# Main.net
KiCad netlist of a schematic drawn in Altium Designer
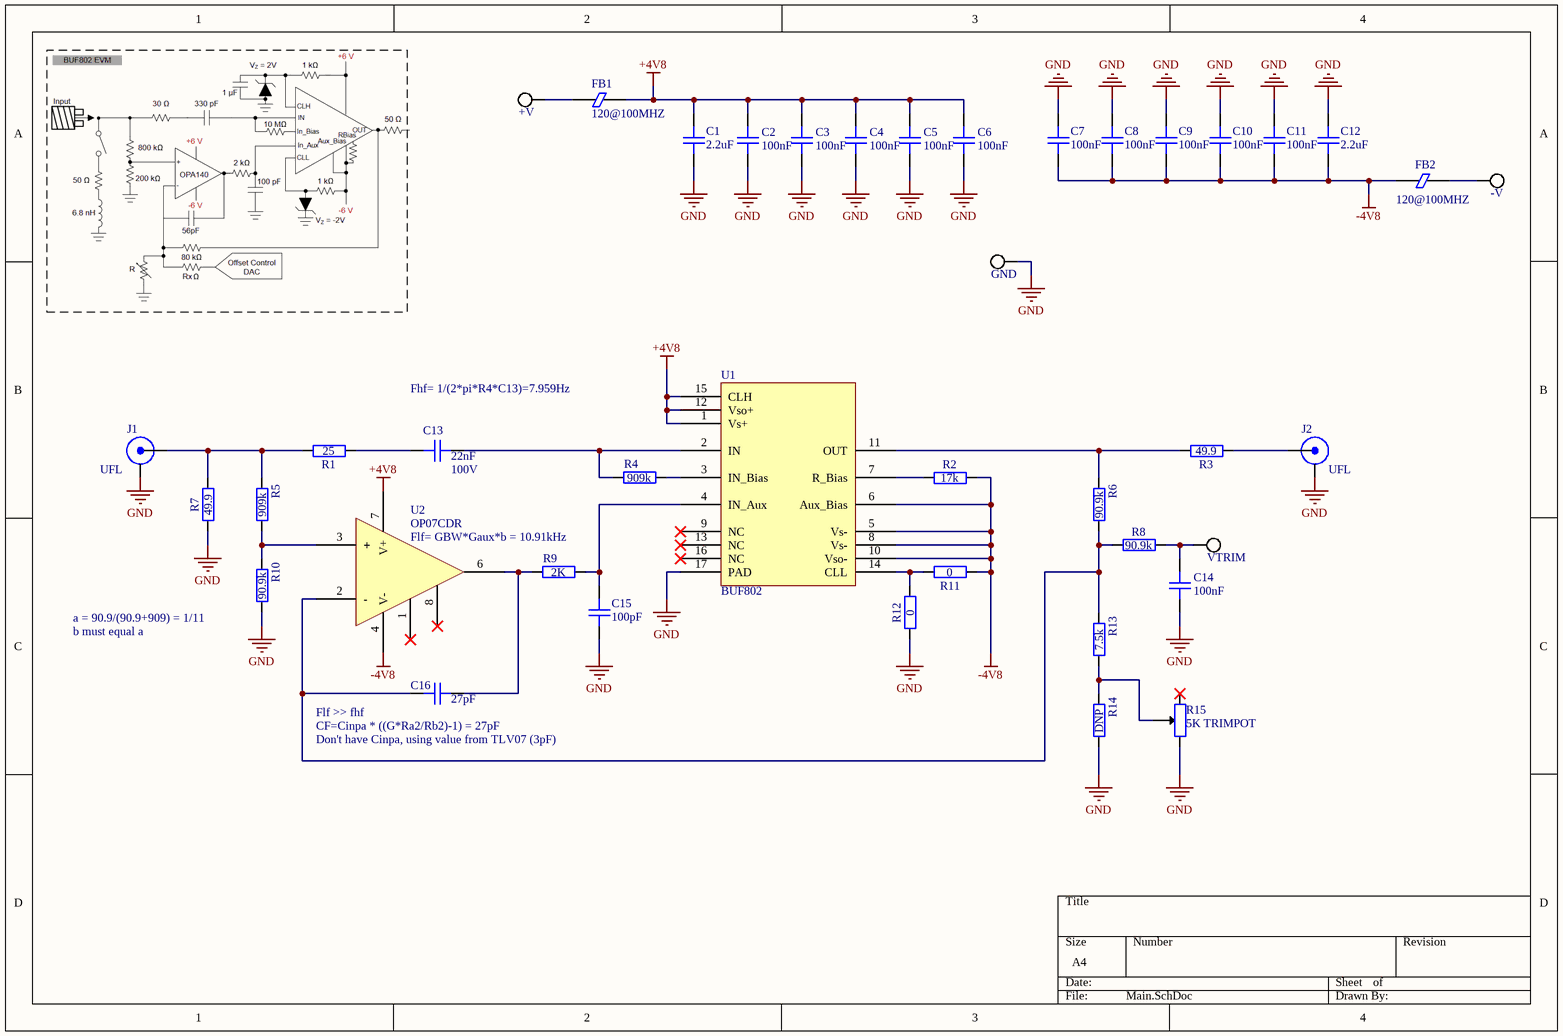
[diagram p0: Main.SchDoc]

(export (version "E")
  (design (tool "Eeschema 10.0.6"))
  (components
    (comp (ref "+V") (value "PCB") (footprint "GEN_TP_PCB") (libsource (lib "DSO") (part "TP PCB 1mm")))
    (comp (ref "-V") (value "PCB") (footprint "GEN_TP_PCB") (libsource (lib "DSO") (part "TP PCB 1mm")))
    (comp (ref "C1")
      (value "2.2uF")
      (footprint "GEN_C_0402")
      (libsource (lib "DSO") (part "CAP 2.2uF 10V X5R 0402"))
    )
    (comp (ref "C2")
      (value "100nF")
      (footprint "GEN_C_0402")
      (libsource (lib "DSO") (part "CAP 100nF 16V X7R 0402"))
    )
    (comp (ref "C3")
      (value "100nF")
      (footprint "GEN_C_0402")
      (libsource (lib "DSO") (part "CAP 100nF 16V X7R 0402"))
    )
    (comp (ref "C4")
      (value "100nF")
      (footprint "GEN_C_0402")
      (libsource (lib "DSO") (part "CAP 100nF 16V X7R 0402"))
    )
    (comp (ref "C5")
      (value "100nF")
      (footprint "GEN_C_0402")
      (libsource (lib "DSO") (part "CAP 100nF 16V X7R 0402"))
    )
    (comp (ref "C6")
      (value "100nF")
      (footprint "GEN_C_0402")
      (libsource (lib "DSO") (part "CAP 100nF 16V X7R 0402"))
    )
    (comp (ref "C7")
      (value "100nF")
      (footprint "GEN_C_0402")
      (libsource (lib "DSO") (part "CAP 100nF 16V X7R 0402"))
    )
    (comp (ref "C8")
      (value "100nF")
      (footprint "GEN_C_0402")
      (libsource (lib "DSO") (part "CAP 100nF 16V X7R 0402"))
    )
    (comp (ref "C9")
      (value "100nF")
      (footprint "GEN_C_0402")
      (libsource (lib "DSO") (part "CAP 100nF 16V X7R 0402"))
    )
    (comp (ref "C10")
      (value "100nF")
      (footprint "GEN_C_0402")
      (libsource (lib "DSO") (part "CAP 100nF 16V X7R 0402"))
    )
    (comp (ref "C11")
      (value "100nF")
      (footprint "GEN_C_0402")
      (libsource (lib "DSO") (part "CAP 100nF 16V X7R 0402"))
    )
    (comp (ref "C12")
      (value "2.2uF")
      (footprint "GEN_C_0402")
      (libsource (lib "DSO") (part "CAP 2.2uF 10V X5R 0402"))
    )
    (comp (ref "C13")
      (value "22nF")
      (footprint "GEN_C_0603")
      (fields (field (name "VOLTAGE RATING") "100V"))
      (libsource (lib "DSO") (part "CAP 22nF 100V X7R 0603"))
    )
    (comp (ref "C14")
      (value "100nF")
      (footprint "GEN_C_0402")
      (libsource (lib "DSO") (part "CAP 100nF 16V X7R 0402"))
    )
    (comp (ref "C15")
      (value "100pF")
      (footprint "GEN_C_0402")
      (libsource (lib "DSO") (part "CAP 100pF 50V C0G 0402"))
    )
    (comp (ref "C16") (value "27pF") (footprint "GEN_C_0402") (libsource (lib "DSO") (part "CAP TBD 0402")))
    (comp (ref "FB1")
      (value "120@100MHZ")
      (footprint "GEN_R_0402")
      (libsource (lib "DSO") (part "FERRITE BEAD 120 OHM 0402"))
    )
    (comp (ref "FB2")
      (value "120@100MHZ")
      (footprint "GEN_R_0402")
      (libsource (lib "DSO") (part "FERRITE BEAD 120 OHM 0402"))
    )
    (comp (ref "GND") (value "PCB") (footprint "GEN_TP_PCB") (libsource (lib "DSO") (part "TP PCB 1mm")))
    (comp (ref "J1") (value "UFL") (footprint "TE_2334884-1") (libsource (lib "DSO") (part "UFL Jack SMD")))
    (comp (ref "J2") (value "UFL") (footprint "TE_2334884-1") (libsource (lib "DSO") (part "UFL Jack SMD")))
    (comp (ref "R1")
      (value "25")
      (footprint "GEN_R_0402")
      (fields (field (name "TOLERANCE") "1%"))
      (libsource (lib "DSO") (part "RES 49.9 OHM 1% 1/10W 0402"))
    )
    (comp (ref "R2")
      (value "17k")
      (footprint "GEN_R_0402")
      (fields (field (name "TOLERANCE") "1%"))
      (libsource (lib "DSO") (part "RES 100K OHM 1% 1/10W 0402"))
    )
    (comp (ref "R3")
      (value "49.9")
      (footprint "GEN_R_0402")
      (fields (field (name "TOLERANCE") "1%"))
      (libsource (lib "DSO") (part "RES 49.9 OHM 1% 1/10W 0402"))
    )
    (comp (ref "R4")
      (value "909k")
      (footprint "GEN_R_0402")
      (fields (field (name "TOLERANCE") "1%"))
      (libsource (lib "DSO") (part "RES 909K OHM 1% 1/16W 0402"))
    )
    (comp (ref "R5")
      (value "909k")
      (footprint "GEN_R_0402")
      (fields (field (name "TOLERANCE") "1%"))
      (libsource (lib "") (part "RES 909K OHM 1% 1/16W 0402_1"))
    )
    (comp (ref "R6")
      (value "90.9k")
      (footprint "GEN_R_0402")
      (fields (field (name "TOLERANCE") "1%"))
      (libsource (lib "DSO") (part "RES 90.9K OHM 1% 1/16W 0402"))
    )
    (comp (ref "R7")
      (value "49.9")
      (footprint "GEN_R_0402")
      (fields (field (name "TOLERANCE") "1%"))
      (libsource (lib "") (part "RES 49.9 OHM 1% 1/10W 0402_1"))
    )
    (comp (ref "R8")
      (value "90.9k")
      (footprint "GEN_R_0402")
      (fields (field (name "TOLERANCE") "1%"))
      (libsource (lib "") (part "RES 90.9K OHM 1% 1/16W 0402_1"))
    )
    (comp (ref "R9")
      (value "2K")
      (footprint "GEN_R_0402")
      (fields (field (name "TOLERANCE") "1%"))
      (libsource (lib "DSO") (part "RES 2K OHM 1% 1/16W 0402"))
    )
    (comp (ref "R10")
      (value "90.9k")
      (footprint "GEN_R_0402")
      (fields (field (name "TOLERANCE") "1%"))
      (libsource (lib "DSO") (part "RES 90.9K OHM 1% 1/16W 0402"))
    )
    (comp (ref "R11")
      (value "0")
      (footprint "GEN_R_0402")
      (libsource (lib "DSO") (part "RES 0 OHM 1/16W 0402"))
    )
    (comp (ref "R12")
      (value "0")
      (footprint "GEN_R_0402")
      (libsource (lib "") (part "RES 0 OHM 1/16W 0402_1"))
    )
    (comp (ref "R13")
      (value "7.5k")
      (footprint "GEN_R_0402")
      (fields (field (name "TOLERANCE") "1%"))
      (libsource (lib "DSO") (part "RES 10K OHM 1% 1/10W 0402"))
    )
    (comp (ref "R14")
      (value "DNP")
      (footprint "GEN_R_0402")
      (fields (field (name "TOLERANCE") "1%"))
      (libsource (lib "DSO") (part "RES DNP 0402"))
    )
    (comp (ref "R15")
      (value "5K TRIMPOT")
      (footprint "BOU_3mm_POT")
      (fields (field (name "TOLERANCE") "1%"))
      (libsource (lib "DSO") (part "TRIMMER 5K OHM 0.1W J LEAD TOP"))
    )
    (comp (ref "U1")
      (value "BUF802")
      (footprint "TI_VQFN_RGT0016C")
      (libsource (lib "DSO") (part "IC BUFFER AMP BUF802"))
    )
    (comp (ref "U2")
      (value "OP07CDR")
      (footprint "TI_SOIC8_D0008A")
      (libsource (lib "DSO") (part "IC OPAMP OP07CDR"))
    )
    (comp (ref "VTRIM") (value "PCB") (footprint "GEN_TP_PCB") (libsource (lib "DSO") (part "TP PCB 1mm")))
  )
  (nets
    (net (code "1") (name "+4V8") (class "Default")
      (node (ref "C1") (pin "2") (pinfunction "2_2") (pintype "passive"))
      (node (ref "C2") (pin "1") (pinfunction "1_1") (pintype "passive"))
      (node (ref "C3") (pin "1") (pinfunction "1_1") (pintype "passive"))
      (node (ref "C4") (pin "1") (pinfunction "1_1") (pintype "passive"))
      (node (ref "C5") (pin "2") (pinfunction "2_2") (pintype "passive"))
      (node (ref "C6") (pin "2") (pinfunction "2_2") (pintype "passive"))
      (node (ref "FB1") (pin "2") (pinfunction "2_2") (pintype "passive"))
      (node (ref "U1") (pin "1") (pinfunction "Vs+_1") (pintype "passive"))
      (node (ref "U1") (pin "12") (pinfunction "Vso+_12") (pintype "passive"))
      (node (ref "U1") (pin "15") (pinfunction "CLH_15") (pintype "passive"))
      (node (ref "U2") (pin "7") (pinfunction "V+_7") (pintype "passive"))
    )
    (net (code "2") (name "-4V8") (class "Default")
      (node (ref "C10") (pin "1") (pinfunction "1_1") (pintype "passive"))
      (node (ref "C11") (pin "1") (pinfunction "1_1") (pintype "passive"))
      (node (ref "C12") (pin "2") (pinfunction "2_2") (pintype "passive"))
      (node (ref "C7") (pin "2") (pinfunction "2_2") (pintype "passive"))
      (node (ref "C8") (pin "2") (pinfunction "2_2") (pintype "passive"))
      (node (ref "C9") (pin "1") (pinfunction "1_1") (pintype "passive"))
      (node (ref "FB2") (pin "1") (pinfunction "1_1") (pintype "passive"))
      (node (ref "R11") (pin "1") (pinfunction "1_1") (pintype "passive"))
      (node (ref "R2") (pin "2") (pinfunction "2_2") (pintype "passive"))
      (node (ref "U1") (pin "10") (pinfunction "Vso-_10") (pintype "passive"))
      (node (ref "U1") (pin "5") (pinfunction "Vs-_5") (pintype "passive"))
      (node (ref "U1") (pin "6") (pinfunction "Aux_Bias_6") (pintype "passive"))
      (node (ref "U1") (pin "8") (pinfunction "Vs-_8") (pintype "passive"))
      (node (ref "U2") (pin "4") (pinfunction "V-_4") (pintype "passive"))
    )
    (net (code "3") (name "GND") (class "Default")
      (node (ref "C1") (pin "1") (pinfunction "1_1") (pintype "passive"))
      (node (ref "C10") (pin "2") (pinfunction "2_2") (pintype "passive"))
      (node (ref "C11") (pin "2") (pinfunction "2_2") (pintype "passive"))
      (node (ref "C12") (pin "1") (pinfunction "1_1") (pintype "passive"))
      (node (ref "C14") (pin "2") (pinfunction "2_2") (pintype "passive"))
      (node (ref "C15") (pin "1") (pinfunction "1_1") (pintype "passive"))
      (node (ref "C2") (pin "2") (pinfunction "2_2") (pintype "passive"))
      (node (ref "C3") (pin "2") (pinfunction "2_2") (pintype "passive"))
      (node (ref "C4") (pin "2") (pinfunction "2_2") (pintype "passive"))
      (node (ref "C5") (pin "1") (pinfunction "1_1") (pintype "passive"))
      (node (ref "C6") (pin "1") (pinfunction "1_1") (pintype "passive"))
      (node (ref "C7") (pin "1") (pinfunction "1_1") (pintype "passive"))
      (node (ref "C8") (pin "1") (pinfunction "1_1") (pintype "passive"))
      (node (ref "C9") (pin "2") (pinfunction "2_2") (pintype "passive"))
      (node (ref "GND") (pin "1") (pinfunction "1_1") (pintype "passive"))
      (node (ref "J1") (pin "2") (pinfunction "SHIELD_2") (pintype "passive"))
      (node (ref "J2") (pin "2") (pinfunction "SHIELD_2") (pintype "passive"))
      (node (ref "R10") (pin "1") (pinfunction "1_1") (pintype "passive"))
      (node (ref "R12") (pin "1") (pinfunction "1_1") (pintype "passive"))
      (node (ref "R14") (pin "1") (pinfunction "1_1") (pintype "passive"))
      (node (ref "R15") (pin "3") (pinfunction "3_3") (pintype "passive"))
      (node (ref "R7") (pin "1") (pinfunction "1_1") (pintype "passive"))
      (node (ref "U1") (pin "17") (pinfunction "PAD_17") (pintype "passive"))
    )
    (net (code "4") (name "Net-(+V-Pad1)") (class "Default")
      (node (ref "+V") (pin "1") (pinfunction "1_1") (pintype "passive"))
      (node (ref "FB1") (pin "1") (pinfunction "1_1") (pintype "passive"))
    )
    (net (code "5") (name "Net-(-V-Pad1)") (class "Default")
      (node (ref "-V") (pin "1") (pinfunction "1_1") (pintype "passive"))
      (node (ref "FB2") (pin "2") (pinfunction "2_2") (pintype "passive"))
    )
    (net (code "6") (name "Net-(C13-Pad2)") (class "Default")
      (node (ref "C13") (pin "2") (pinfunction "2_2") (pintype "passive"))
      (node (ref "R1") (pin "2") (pinfunction "2_2") (pintype "passive"))
    )
    (net (code "7") (name "Net-(C14-Pad1)") (class "Default")
      (node (ref "C14") (pin "1") (pinfunction "1_1") (pintype "passive"))
      (node (ref "R8") (pin "1") (pinfunction "1_1") (pintype "passive"))
      (node (ref "VTRIM") (pin "1") (pinfunction "1_1") (pintype "passive"))
    )
    (net (code "8") (name "Net-(J1-Signal)") (class "Default")
      (node (ref "J1") (pin "1") (pinfunction "Signal_1") (pintype "passive"))
      (node (ref "R1") (pin "1") (pinfunction "1_1") (pintype "passive"))
      (node (ref "R5") (pin "2") (pinfunction "2_2") (pintype "passive"))
      (node (ref "R7") (pin "2") (pinfunction "2_2") (pintype "passive"))
    )
    (net (code "9") (name "Net-(J2-Signal)") (class "Default")
      (node (ref "J2") (pin "1") (pinfunction "Signal_1") (pintype "passive"))
      (node (ref "R3") (pin "2") (pinfunction "2_2") (pintype "passive"))
    )
    (net (code "10") (name "Net-(R13-Pad1)") (class "Default")
      (node (ref "R13") (pin "1") (pinfunction "1_1") (pintype "passive"))
      (node (ref "R14") (pin "2") (pinfunction "2_2") (pintype "passive"))
      (node (ref "R15") (pin "2") (pinfunction "2_2") (pintype "passive"))
    )
    (net (code "11") (name "Net-(U1-CLL)") (class "Default")
      (node (ref "R11") (pin "2") (pinfunction "2_2") (pintype "passive"))
      (node (ref "R12") (pin "2") (pinfunction "2_2") (pintype "passive"))
      (node (ref "U1") (pin "14") (pinfunction "CLL_14") (pintype "passive"))
    )
    (net (code "12") (name "Net-(U1-IN)") (class "Default")
      (node (ref "C13") (pin "1") (pinfunction "1_1") (pintype "passive"))
      (node (ref "R4") (pin "2") (pinfunction "2_2") (pintype "passive"))
      (node (ref "U1") (pin "2") (pinfunction "IN_2") (pintype "passive"))
    )
    (net (code "13") (name "Net-(U1-IN_Aux)") (class "Default")
      (node (ref "C15") (pin "2") (pinfunction "2_2") (pintype "passive"))
      (node (ref "R9") (pin "1") (pinfunction "1_1") (pintype "passive"))
      (node (ref "U1") (pin "4") (pinfunction "IN_Aux_4") (pintype "passive"))
    )
    (net (code "14") (name "Net-(U1-IN_Bias)") (class "Default")
      (node (ref "R4") (pin "1") (pinfunction "1_1") (pintype "passive"))
      (node (ref "U1") (pin "3") (pinfunction "IN_Bias_3") (pintype "passive"))
    )
    (net (code "15") (name "Net-(U1-OUT)") (class "Default")
      (node (ref "R3") (pin "1") (pinfunction "1_1") (pintype "passive"))
      (node (ref "R6") (pin "2") (pinfunction "2_2") (pintype "passive"))
      (node (ref "U1") (pin "11") (pinfunction "OUT_11") (pintype "passive"))
    )
    (net (code "16") (name "Net-(U1-R_Bias)") (class "Default")
      (node (ref "R2") (pin "1") (pinfunction "1_1") (pintype "passive"))
      (node (ref "U1") (pin "7") (pinfunction "R_Bias_7") (pintype "passive"))
    )
    (net (code "17") (name "Net-(U2-+)") (class "Default")
      (node (ref "R10") (pin "2") (pinfunction "2_2") (pintype "passive"))
      (node (ref "R5") (pin "1") (pinfunction "1_1") (pintype "passive"))
      (node (ref "U2") (pin "3") (pinfunction "+_3") (pintype "passive"))
    )
    (net (code "18") (name "Net-(U2--)") (class "Default")
      (node (ref "C16") (pin "2") (pinfunction "2_2") (pintype "passive"))
      (node (ref "R13") (pin "2") (pinfunction "2_2") (pintype "passive"))
      (node (ref "R6") (pin "1") (pinfunction "1_1") (pintype "passive"))
      (node (ref "R8") (pin "2") (pinfunction "2_2") (pintype "passive"))
      (node (ref "U2") (pin "2") (pinfunction "-_2") (pintype "passive"))
    )
    (net (code "19") (name "Net-(U2-OUT)") (class "Default")
      (node (ref "C16") (pin "1") (pinfunction "1_1") (pintype "passive"))
      (node (ref "R9") (pin "2") (pinfunction "2_2") (pintype "passive"))
      (node (ref "U2") (pin "6") (pinfunction "OUT_6") (pintype "passive"))
    )
    (net (code "20") (name "unconnected-(R15-Pad1)") (class "Default")
      (node (ref "R15") (pin "1") (pinfunction "1_1") (pintype "passive+no_connect"))
    )
    (net (code "21") (name "unconnected-(U1-NC-Pad9)") (class "Default")
      (node (ref "U1") (pin "9") (pinfunction "NC_9") (pintype "passive+no_connect"))
    )
    (net (code "22") (name "unconnected-(U1-NC-Pad13)") (class "Default")
      (node (ref "U1") (pin "13") (pinfunction "NC_13") (pintype "passive+no_connect"))
    )
    (net (code "23") (name "unconnected-(U1-NC-Pad16)") (class "Default")
      (node (ref "U1") (pin "16") (pinfunction "NC_16") (pintype "passive+no_connect"))
    )
    (net (code "24") (name "unconnected-(U2-N1-Pad1)") (class "Default")
      (node (ref "U2") (pin "1") (pinfunction "N1_1") (pintype "passive+no_connect"))
    )
    (net (code "25") (name "unconnected-(U2-N2-Pad8)") (class "Default")
      (node (ref "U2") (pin "8") (pinfunction "N2_8") (pintype "passive+no_connect"))
    )
  )
)
